# MyRIO_Breakout_Gamma2c.net
KiCad netlist of a schematic drawn in EAGLE
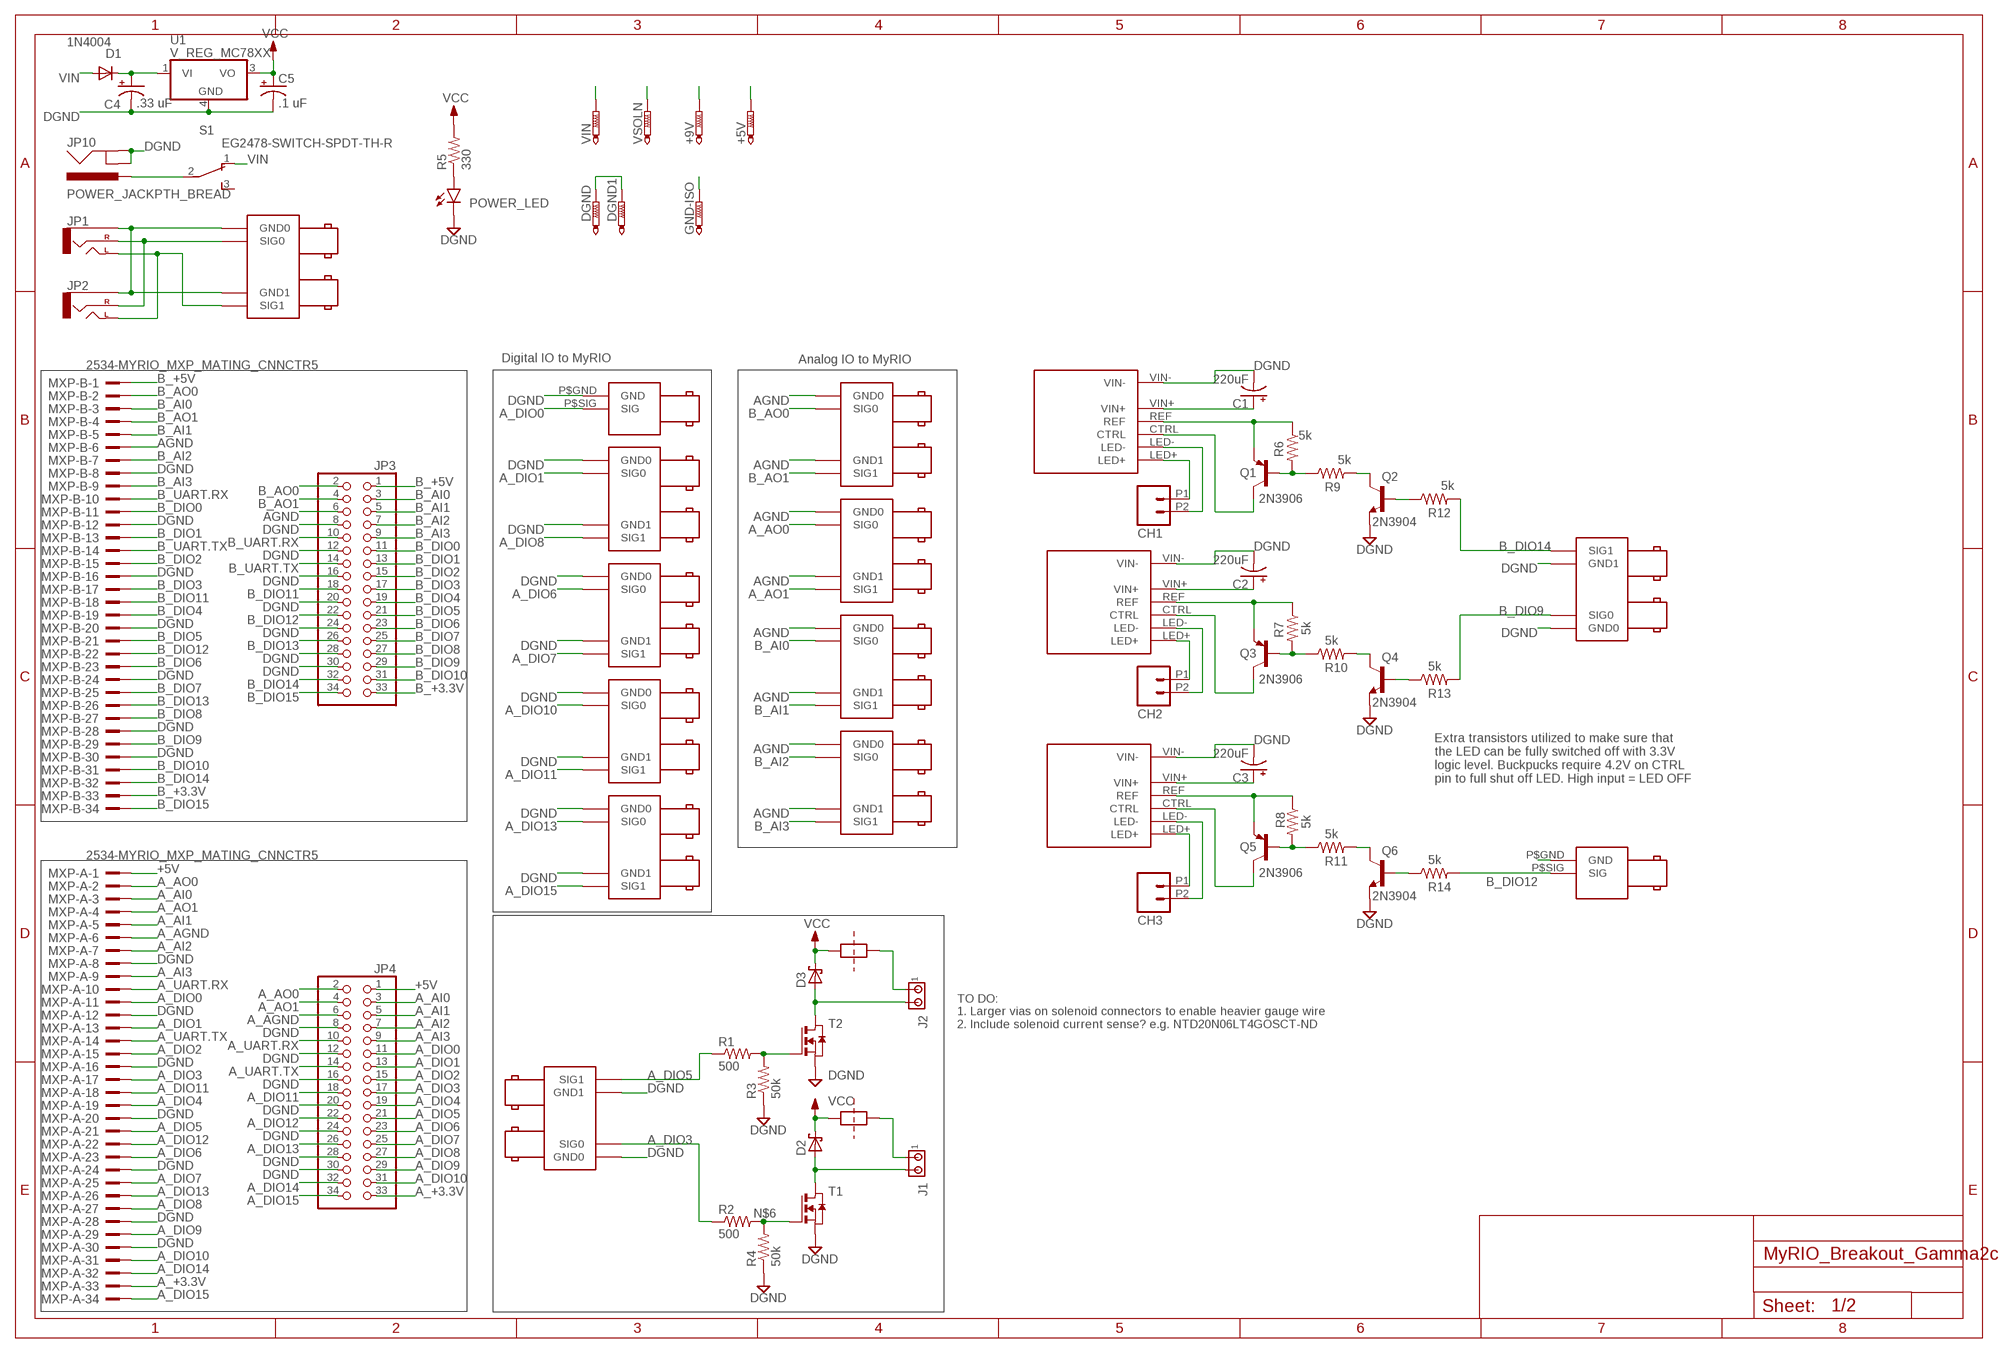
[diagram p0: schematic, sheet 1]
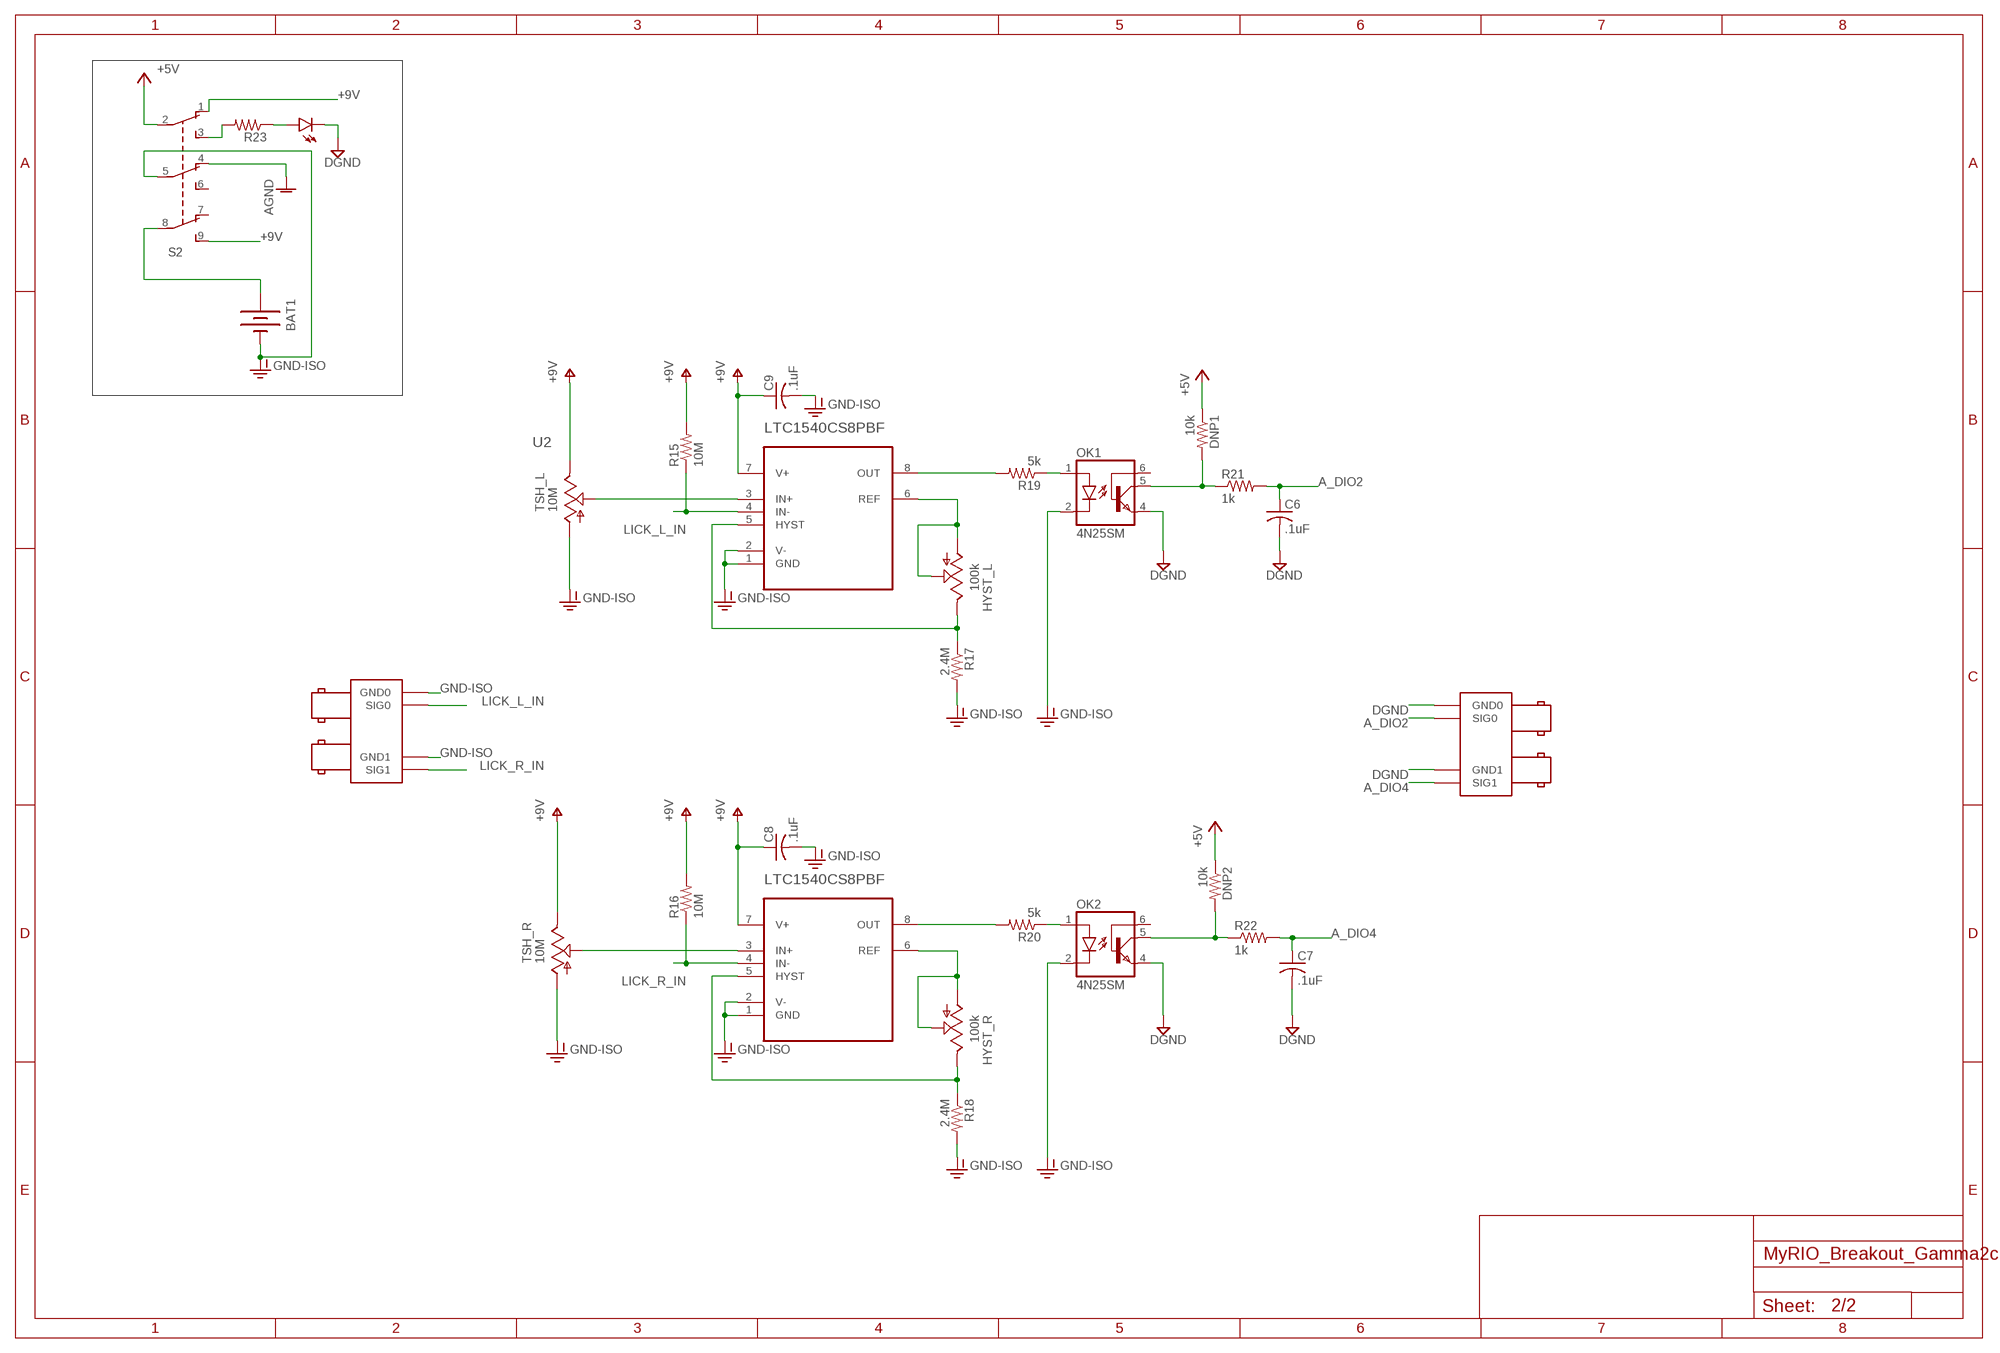
[diagram p1: schematic, sheet 2]

(export (version "E")
  (design (tool "Eeschema 10.0.6"))
  (components
    (comp (ref "BAT1")
      (value "BATTERY9V")
      (footprint "eagle-import:BATTCON_9V")
      (libsource (lib "eagle-import") (part "BATTERY9V"))
    )
    (comp (ref "C6")
      (value ".1uF")
      (footprint "eagle-import:C0805")
      (libsource (lib "eagle-import") (part "C-USC0805"))
    )
    (comp (ref "C7")
      (value ".1uF")
      (footprint "eagle-import:C0805")
      (fields (field (name "SPICEPREFIX") "C"))
      (libsource (lib "eagle-import") (part "C-USC0805"))
    )
    (comp (ref "C8")
      (value ".1uF")
      (footprint "eagle-import:C0805")
      (fields (field (name "SPICEPREFIX") "C"))
      (libsource (lib "eagle-import") (part "C-USC0805"))
    )
    (comp (ref "C9")
      (value ".1uF")
      (footprint "eagle-import:C0805")
      (fields (field (name "SPICEPREFIX") "C"))
      (libsource (lib "eagle-import") (part "C-USC0805"))
    )
    (comp (ref "DNP1")
      (value "10k")
      (footprint "eagle-import:M0805")
      (libsource (lib "eagle-import") (part "R-US_M0805"))
    )
    (comp (ref "DNP2")
      (value "10k")
      (footprint "eagle-import:M0805")
      (fields (field (name "SPICEPREFIX") "R"))
      (libsource (lib "eagle-import") (part "R-US_M0805"))
    )
    (comp (ref "HYST_L")
      (value "100k")
      (footprint "eagle-import:B25P")
      (libsource (lib "eagle-import") (part "TRIM_US-B25P"))
    )
    (comp (ref "HYST_R")
      (value "100k")
      (footprint "eagle-import:B25P")
      (fields (field (name "SPICEPREFIX") "J"))
      (libsource (lib "eagle-import") (part "TRIM_US-B25P"))
    )
    (comp (ref "ISOLATED")
      (value "LED3MM")
      (footprint "eagle-import:LED3MM")
      (libsource (lib "eagle-import") (part "LED3MM"))
    )
    (comp (ref "LICK")
      (value "BNC_RIGHT_ANGLE_DOUBLE")
      (footprint "eagle-import:BNC_RIGHT_ANGLE_DOUBLE")
      (libsource (lib "eagle-import") (part "BNC_RIGHT_ANGLE_DOUBLE"))
    )
    (comp (ref "LICK_INPUTS")
      (value "BNC_RIGHT_ANGLE_DOUBLE")
      (footprint "eagle-import:BNC_RIGHT_ANGLE_DOUBLE")
      (libsource (lib "eagle-import") (part "BNC_RIGHT_ANGLE_DOUBLE"))
    )
    (comp (ref "OK1")
      (value "4N25SM")
      (footprint "eagle-import:DIL6-SMD")
      (fields (field (name "MF") "FAIRCHILD SEMICONDUCTOR"))
      (libsource (lib "eagle-import") (part "4N?MS25"))
    )
    (comp (ref "OK2")
      (value "4N25SM")
      (footprint "eagle-import:DIL6-SMD")
      (fields (field (name "MF") "FAIRCHILD SEMICONDUCTOR") (field (name "SPICEPREFIX") "X"))
      (libsource (lib "eagle-import") (part "4N?MS25"))
    )
    (comp (ref "R15")
      (value "10M")
      (footprint "eagle-import:M0805")
      (fields (field (name "SPICEPREFIX") "R"))
      (libsource (lib "eagle-import") (part "R-US_M0805"))
    )
    (comp (ref "R16")
      (value "10M")
      (footprint "eagle-import:M0805")
      (fields (field (name "SPICEPREFIX") "R"))
      (libsource (lib "eagle-import") (part "R-US_M0805"))
    )
    (comp (ref "R17")
      (value "2.4M")
      (footprint "eagle-import:M0805")
      (libsource (lib "eagle-import") (part "R-US_M0805"))
    )
    (comp (ref "R18")
      (value "2.4M")
      (footprint "eagle-import:M0805")
      (fields (field (name "SPICEPREFIX") "R"))
      (libsource (lib "eagle-import") (part "R-US_M0805"))
    )
    (comp (ref "R19")
      (value "5k")
      (footprint "eagle-import:M0805")
      (libsource (lib "eagle-import") (part "R-US_M0805"))
    )
    (comp (ref "R20")
      (value "5k")
      (footprint "eagle-import:M0805")
      (fields (field (name "SPICEPREFIX") "R"))
      (libsource (lib "eagle-import") (part "R-US_M0805"))
    )
    (comp (ref "R21")
      (value "1k")
      (footprint "eagle-import:M0805")
      (libsource (lib "eagle-import") (part "R-US_M0805"))
    )
    (comp (ref "R22")
      (value "1k")
      (footprint "eagle-import:M0805")
      (fields (field (name "SPICEPREFIX") "R"))
      (libsource (lib "eagle-import") (part "R-US_M0805"))
    )
    (comp (ref "R23")
      (value "330")
      (footprint "eagle-import:0207_10")
      (libsource (lib "eagle-import") (part "R-US_0207/10"))
    )
    (comp (ref "S2")
      (value "SWITCH-3PDT-TH-V")
      (footprint "eagle-import:NKK-M20-9PIN-VERTICAL")
      (libsource (lib "eagle-import") (part "SWITCH-3PDT-TH-V"))
    )
    (comp (ref "TSH_L")
      (value "10M")
      (footprint "eagle-import:B25P")
      (libsource (lib "eagle-import") (part "TRIM_US-B25P"))
    )
    (comp (ref "TSH_R")
      (value "10M")
      (footprint "eagle-import:B25P")
      (libsource (lib "eagle-import") (part "TRIM_US-B25P"))
    )
    (comp (ref "U2")
      (value "LTC1540CS8PBF")
      (footprint "eagle-import:SOIC127P600X175-8N")
      (fields (field (name "MF") "Linear Technology/Analog") (field (name "MP") "LTC1540CS8#PBF"))
      (libsource (lib "eagle-import") (part "LTC1540CS8PBF"))
    )
    (comp (ref "U3")
      (value "LTC1540CS8PBF")
      (footprint "eagle-import:SOIC127P600X175-8N")
      (fields
        (field (name "MF") "Linear Technology/Analog")
        (field (name "MP") "LTC1540CS8#PBF")
        (field (name "SPICEPREFIX") "X")
      )
      (libsource (lib "eagle-import") (part "LTC1540CS8PBF"))
    )
    (comp (ref "+5V")
      (value "PTR1PAD1-13Y")
      (footprint "eagle-import:P1-13Y")
      (libsource (lib "eagle-import") (part "PTR1PAD1-13Y"))
    )
    (comp (ref "+9V")
      (value "PTR1PAD1-13Y")
      (footprint "eagle-import:P1-13Y")
      (libsource (lib "eagle-import") (part "PTR1PAD1-13Y"))
    )
    (comp (ref "AAO_0,1")
      (value "BNC_RIGHT_ANGLE_DOUBLE")
      (footprint "eagle-import:BNC_RIGHT_ANGLE_DOUBLE")
      (libsource (lib "eagle-import") (part "BNC_RIGHT_ANGLE_DOUBLE"))
    )
    (comp (ref "ACTV_REC")
      (value "BNC_RIGHT_ANGLE")
      (footprint "eagle-import:BNC_RIGHT_ANGLE")
      (libsource (lib "eagle-import") (part "BNC_RIGHT_ANGLE"))
    )
    (comp (ref "AUDIO")
      (value "BNC_RIGHT_ANGLE_DOUBLE")
      (footprint "eagle-import:BNC_RIGHT_ANGLE_DOUBLE")
      (libsource (lib "eagle-import") (part "BNC_RIGHT_ANGLE_DOUBLE"))
    )
    (comp (ref "BAI_0,1")
      (value "BNC_RIGHT_ANGLE_DOUBLE")
      (footprint "eagle-import:BNC_RIGHT_ANGLE_DOUBLE")
      (libsource (lib "eagle-import") (part "BNC_RIGHT_ANGLE_DOUBLE"))
    )
    (comp (ref "BAI_2,3")
      (value "BNC_RIGHT_ANGLE_DOUBLE")
      (footprint "eagle-import:BNC_RIGHT_ANGLE_DOUBLE")
      (libsource (lib "eagle-import") (part "BNC_RIGHT_ANGLE_DOUBLE"))
    )
    (comp (ref "BAO_0,1")
      (value "BNC_RIGHT_ANGLE_DOUBLE")
      (footprint "eagle-import:BNC_RIGHT_ANGLE_DOUBLE")
      (libsource (lib "eagle-import") (part "BNC_RIGHT_ANGLE_DOUBLE"))
    )
    (comp (ref "BUCKPUCK1")
      (value "BUCKPUCK-350-I")
      (footprint "eagle-import:BUCKPUCK_I")
      (libsource (lib "eagle-import") (part "BUCKPUCK--?I350"))
    )
    (comp (ref "BUCKPUCK2")
      (value "BUCKPUCK-350-I")
      (footprint "eagle-import:BUCKPUCK_I")
      (libsource (lib "eagle-import") (part "BUCKPUCK--?I350"))
    )
    (comp (ref "BUCKPUCK3")
      (value "BUCKPUCK-350-I")
      (footprint "eagle-import:BUCKPUCK_I")
      (libsource (lib "eagle-import") (part "BUCKPUCK--?I350"))
    )
    (comp (ref "C1")
      (value "220uF")
      (footprint "eagle-import:E5-10,5")
      (libsource (lib "eagle-import") (part "CPOL-USE5-10.5"))
    )
    (comp (ref "C2")
      (value "220uF")
      (footprint "eagle-import:E5-10,5")
      (libsource (lib "eagle-import") (part "CPOL-USE5-10.5"))
    )
    (comp (ref "C3")
      (value "220uF")
      (footprint "eagle-import:E5-10,5")
      (libsource (lib "eagle-import") (part "CPOL-USE5-10.5"))
    )
    (comp (ref "C4")
      (value ".33 uF")
      (footprint "eagle-import:E2,5-5")
      (libsource (lib "eagle-import") (part "CPOL-USE2.5-5"))
    )
    (comp (ref "C5")
      (value ".1 uF")
      (footprint "eagle-import:E2,5-5")
      (libsource (lib "eagle-import") (part "CPOL-USE2.5-5"))
    )
    (comp (ref "CAMERA")
      (value "BNC_RIGHT_ANGLE_DOUBLE")
      (footprint "eagle-import:BNC_RIGHT_ANGLE_DOUBLE")
      (libsource (lib "eagle-import") (part "BNC_RIGHT_ANGLE_DOUBLE"))
    )
    (comp (ref "CH1")
      (value "M022.54MM_SCREWTERM")
      (footprint "eagle-import:1X02_2.54_SCREWTERM")
      (libsource (lib "eagle-import") (part "M022.54MM_SCREWTERM"))
    )
    (comp (ref "CH2")
      (value "M022.54MM_SCREWTERM")
      (footprint "eagle-import:1X02_2.54_SCREWTERM")
      (libsource (lib "eagle-import") (part "M022.54MM_SCREWTERM"))
    )
    (comp (ref "CH3")
      (value "M022.54MM_SCREWTERM")
      (footprint "eagle-import:1X02_2.54_SCREWTERM")
      (libsource (lib "eagle-import") (part "M022.54MM_SCREWTERM"))
    )
    (comp (ref "D1")
      (value "1N4004")
      (footprint "eagle-import:DO41-10")
      (libsource (lib "eagle-import") (part "1N4004"))
    )
    (comp (ref "D2")
      (value "SCHOTTKY-DIODE")
      (footprint "eagle-import:DIODE_SMB")
      (libsource (lib "eagle-import") (part "SCHOTTKY-DIODE"))
    )
    (comp (ref "D3")
      (value "SCHOTTKY-DIODE")
      (footprint "eagle-import:DIODE_SMB")
      (libsource (lib "eagle-import") (part "SCHOTTKY-DIODE"))
    )
    (comp (ref "DGND")
      (value "PTR1PAD1-13Y")
      (footprint "eagle-import:P1-13Y")
      (libsource (lib "eagle-import") (part "PTR1PAD1-13Y"))
    )
    (comp (ref "DGND1")
      (value "PTR1PAD1-13Y")
      (footprint "eagle-import:P1-13Y")
      (libsource (lib "eagle-import") (part "PTR1PAD1-13Y"))
    )
    (comp (ref "D_FREE1_2")
      (value "BNC_RIGHT_ANGLE_DOUBLE")
      (footprint "eagle-import:BNC_RIGHT_ANGLE_DOUBLE")
      (libsource (lib "eagle-import") (part "BNC_RIGHT_ANGLE_DOUBLE"))
    )
    (comp (ref "D_FREE3_4")
      (value "BNC_RIGHT_ANGLE_DOUBLE")
      (footprint "eagle-import:BNC_RIGHT_ANGLE_DOUBLE")
      (libsource (lib "eagle-import") (part "BNC_RIGHT_ANGLE_DOUBLE"))
    )
    (comp (ref "GND-ISO")
      (value "PTR1PAD1-13Y")
      (footprint "eagle-import:P1-13Y")
      (libsource (lib "eagle-import") (part "PTR1PAD1-13Y"))
    )
    (comp (ref "J1")
      (value "MTA02-100")
      (footprint "eagle-import:10X02MTA")
      (libsource (lib "eagle-import") (part "MTA02-100"))
    )
    (comp (ref "J2")
      (value "MTA02-100")
      (footprint "eagle-import:10X02MTA")
      (libsource (lib "eagle-import") (part "MTA02-100"))
    )
    (comp (ref "JP1")
      (value "AUDIO-JACKPTH")
      (footprint "eagle-import:AUDIO-JACK")
      (libsource (lib "eagle-import") (part "AUDIO-JACKPTH"))
    )
    (comp (ref "JP2")
      (value "AUDIO-JACKPTH")
      (footprint "eagle-import:AUDIO-JACK")
      (libsource (lib "eagle-import") (part "AUDIO-JACKPTH"))
    )
    (comp (ref "JP3")
      (value "PINHD-2X17")
      (footprint "eagle-import:2X17")
      (libsource (lib "eagle-import") (part "PINHD-2X17"))
    )
    (comp (ref "JP4")
      (value "PINHD-2X17")
      (footprint "eagle-import:2X17")
      (libsource (lib "eagle-import") (part "PINHD-2X17"))
    )
    (comp (ref "JP5")
      (value "CUTABLE_RESISTOR_JUMPER1206")
      (footprint "eagle-import:1206_WITH_TRACE")
      (libsource (lib "eagle-import") (part "CUTABLE_RESISTOR_JUMPER1206"))
    )
    (comp (ref "JP6")
      (value "CUTABLE_RESISTOR_JUMPER1206")
      (footprint "eagle-import:1206_WITH_TRACE")
      (libsource (lib "eagle-import") (part "CUTABLE_RESISTOR_JUMPER1206"))
    )
    (comp (ref "JP10")
      (value "POWER_JACKPTH_BREAD")
      (footprint "eagle-import:POWER_JACK_PTH_BREAD")
      (libsource (lib "eagle-import") (part "POWER_JACKPTH_BREAD"))
    )
    (comp (ref "LED_CUE_3")
      (value "BNC_RIGHT_ANGLE")
      (footprint "eagle-import:BNC_RIGHT_ANGLE")
      (libsource (lib "eagle-import") (part "BNC_RIGHT_ANGLE"))
    )
    (comp (ref "LED_MASK_1,2")
      (value "BNC_RIGHT_ANGLE_DOUBLE")
      (footprint "eagle-import:BNC_RIGHT_ANGLE_DOUBLE")
      (libsource (lib "eagle-import") (part "BNC_RIGHT_ANGLE_DOUBLE"))
    )
    (comp (ref "MXP-A")
      (value "2534-MYRIO_MXP_MATING_CNNCTR5")
      (footprint "eagle-import:PAK100_2500-5-34-MXP_CONNCTR")
      (libsource (lib "eagle-import") (part "2534-MYRIO_MXP_MATING_CNNCTR5"))
    )
    (comp (ref "MXP-B")
      (value "2534-MYRIO_MXP_MATING_CNNCTR5")
      (footprint "eagle-import:PAK100_2500-5-34-MXP_CONNCTR")
      (libsource (lib "eagle-import") (part "2534-MYRIO_MXP_MATING_CNNCTR5"))
    )
    (comp (ref "POWER_LED")
      (value "LED3MM")
      (footprint "eagle-import:LED3MM")
      (libsource (lib "eagle-import") (part "LED3MM"))
    )
    (comp (ref "Q1")
      (value "2N3906")
      (footprint "eagle-import:SOT23-BEC")
      (libsource (lib "eagle-import") (part "-PNP-SOT23-BECMMBT3906LT1"))
    )
    (comp (ref "Q2")
      (value "2N3904")
      (footprint "eagle-import:SOT23-BEC")
      (libsource (lib "eagle-import") (part "-NPN-SOT23-BECMMBT3904LT1"))
    )
    (comp (ref "Q3")
      (value "2N3906")
      (footprint "eagle-import:SOT23-BEC")
      (libsource (lib "eagle-import") (part "-PNP-SOT23-BECMMBT3906LT1"))
    )
    (comp (ref "Q4")
      (value "2N3904")
      (footprint "eagle-import:SOT23-BEC")
      (libsource (lib "eagle-import") (part "-NPN-SOT23-BECMMBT3904LT1"))
    )
    (comp (ref "Q5")
      (value "2N3906")
      (footprint "eagle-import:SOT23-BEC")
      (libsource (lib "eagle-import") (part "-PNP-SOT23-BECMMBT3906LT1"))
    )
    (comp (ref "Q6")
      (value "2N3904")
      (footprint "eagle-import:SOT23-BEC")
      (libsource (lib "eagle-import") (part "-NPN-SOT23-BECMMBT3904LT1"))
    )
    (comp (ref "R1")
      (value "500")
      (footprint "eagle-import:M1206")
      (libsource (lib "eagle-import") (part "R-US_M1206"))
    )
    (comp (ref "R2")
      (value "500")
      (footprint "eagle-import:M1206")
      (libsource (lib "eagle-import") (part "R-US_M1206"))
    )
    (comp (ref "R3")
      (value "50k")
      (footprint "eagle-import:M1206")
      (libsource (lib "eagle-import") (part "R-US_M1206"))
    )
    (comp (ref "R4")
      (value "50k")
      (footprint "eagle-import:M1206")
      (libsource (lib "eagle-import") (part "R-US_M1206"))
    )
    (comp (ref "R5")
      (value "330")
      (footprint "eagle-import:0207_10")
      (libsource (lib "eagle-import") (part "R-US_0207/10"))
    )
    (comp (ref "R6")
      (value "5k")
      (footprint "eagle-import:0805S")
      (libsource (lib "eagle-import") (part "RESISTOR_SM0805S"))
    )
    (comp (ref "R7")
      (value "5k")
      (footprint "eagle-import:0805S")
      (libsource (lib "eagle-import") (part "RESISTOR_SM0805S"))
    )
    (comp (ref "R8")
      (value "5k")
      (footprint "eagle-import:0805S")
      (libsource (lib "eagle-import") (part "RESISTOR_SM0805S"))
    )
    (comp (ref "R9")
      (value "5k")
      (footprint "eagle-import:0805S")
      (libsource (lib "eagle-import") (part "RESISTOR_SM0805S"))
    )
    (comp (ref "R10")
      (value "5k")
      (footprint "eagle-import:0805S")
      (libsource (lib "eagle-import") (part "RESISTOR_SM0805S"))
    )
    (comp (ref "R11")
      (value "5k")
      (footprint "eagle-import:0805S")
      (libsource (lib "eagle-import") (part "RESISTOR_SM0805S"))
    )
    (comp (ref "R12")
      (value "5k")
      (footprint "eagle-import:0805S")
      (libsource (lib "eagle-import") (part "RESISTOR_SM0805S"))
    )
    (comp (ref "R13")
      (value "5k")
      (footprint "eagle-import:0805S")
      (libsource (lib "eagle-import") (part "RESISTOR_SM0805S"))
    )
    (comp (ref "R14")
      (value "5k")
      (footprint "eagle-import:0805S")
      (libsource (lib "eagle-import") (part "RESISTOR_SM0805S"))
    )
    (comp (ref "S1")
      (value "EG2478-SWITCH-SPDT-TH-R")
      (footprint "eagle-import:ESWITCH_500-SSP1M6")
      (libsource (lib "eagle-import") (part "EG2478-SWITCH-SPDT-TH-R"))
    )
    (comp (ref "SHUTTER")
      (value "BNC_RIGHT_ANGLE_DOUBLE")
      (footprint "eagle-import:BNC_RIGHT_ANGLE_DOUBLE")
      (libsource (lib "eagle-import") (part "BNC_RIGHT_ANGLE_DOUBLE"))
    )
    (comp (ref "SLN")
      (value "BNC_RIGHT_ANGLE_DOUBLE")
      (footprint "eagle-import:BNC_RIGHT_ANGLE_DOUBLE")
      (libsource (lib "eagle-import") (part "BNC_RIGHT_ANGLE_DOUBLE"))
    )
    (comp (ref "T1")
      (value "NMOSSOT223")
      (footprint "eagle-import:SOT223")
      (libsource (lib "eagle-import") (part "NMOSSOT223"))
    )
    (comp (ref "T2")
      (value "NMOSSOT223")
      (footprint "eagle-import:SOT223")
      (libsource (lib "eagle-import") (part "NMOSSOT223"))
    )
    (comp (ref "U1")
      (value "V_REG_MC78XX")
      (footprint "eagle-import:DPAK")
      (libsource (lib "eagle-import") (part "V_REG_MC78XX"))
    )
    (comp (ref "VIN")
      (value "PTR1PAD1-13Y")
      (footprint "eagle-import:P1-13Y")
      (libsource (lib "eagle-import") (part "PTR1PAD1-13Y"))
    )
    (comp (ref "VSOLN")
      (value "PTR1PAD1-13Y")
      (footprint "eagle-import:P1-13Y")
      (libsource (lib "eagle-import") (part "PTR1PAD1-13Y"))
    )
  )
  (nets
    (net (code "1") (name "+5V") (class "Default")
      (node (ref "+5V") (pin "TP") (pinfunction "TP_TP") (pintype "input"))
      (node (ref "DNP1") (pin "1") (pinfunction "1_1") (pintype "passive"))
      (node (ref "DNP2") (pin "1") (pinfunction "1_1") (pintype "passive"))
      (node (ref "JP4") (pin "1") (pinfunction "1_1") (pintype "passive"))
      (node (ref "MXP-A") (pin "1") (pinfunction "KL_1") (pintype "passive"))
      (node (ref "S2") (pin "2") (pinfunction "P1_2") (pintype "passive"))
    )
    (net (code "2") (name "+9V") (class "Default")
      (node (ref "+9V") (pin "TP") (pinfunction "TP_TP") (pintype "input"))
      (node (ref "C8") (pin "1") (pinfunction "1_1") (pintype "passive"))
      (node (ref "C9") (pin "1") (pinfunction "1_1") (pintype "passive"))
      (node (ref "R15") (pin "2") (pinfunction "2_2") (pintype "passive"))
      (node (ref "R16") (pin "2") (pinfunction "2_2") (pintype "passive"))
      (node (ref "S2") (pin "1") (pinfunction "O1_1") (pintype "passive"))
      (node (ref "S2") (pin "9") (pinfunction "S3_9") (pintype "passive"))
      (node (ref "TSH_L") (pin "E") (pinfunction "E_E") (pintype "passive"))
      (node (ref "TSH_R") (pin "E") (pinfunction "E_E") (pintype "passive"))
      (node (ref "U2") (pin "7") (pinfunction "V+_7") (pintype "power_in"))
      (node (ref "U3") (pin "7") (pinfunction "V+_7") (pintype "power_in"))
    )
    (net (code "3") (name "AGND") (class "Default")
      (node (ref "AAO_0,1") (pin "P$GND0") (pinfunction "GND0_P$GND0") (pintype "bidirectional"))
      (node (ref "AAO_0,1") (pin "P$GND1") (pinfunction "GND1_P$GND1") (pintype "bidirectional"))
      (node (ref "BAI_0,1") (pin "P$GND0") (pinfunction "GND0_P$GND0") (pintype "bidirectional"))
      (node (ref "BAI_0,1") (pin "P$GND1") (pinfunction "GND1_P$GND1") (pintype "bidirectional"))
      (node (ref "BAI_2,3") (pin "P$GND0") (pinfunction "GND0_P$GND0") (pintype "bidirectional"))
      (node (ref "BAI_2,3") (pin "P$GND1") (pinfunction "GND1_P$GND1") (pintype "bidirectional"))
      (node (ref "BAO_0,1") (pin "P$GND0") (pinfunction "GND0_P$GND0") (pintype "bidirectional"))
      (node (ref "BAO_0,1") (pin "P$GND1") (pinfunction "GND1_P$GND1") (pintype "bidirectional"))
      (node (ref "JP3") (pin "6") (pinfunction "6_6") (pintype "passive"))
      (node (ref "MXP-B") (pin "6") (pinfunction "KL_6") (pintype "passive"))
      (node (ref "S2") (pin "4") (pinfunction "O2_4") (pintype "passive"))
    )
    (net (code "4") (name "A_+3.3V") (class "Default")
      (node (ref "JP4") (pin "33") (pinfunction "33_33") (pintype "passive"))
      (node (ref "MXP-A") (pin "33") (pinfunction "KL_33") (pintype "passive"))
    )
    (net (code "5") (name "A_AGND") (class "Default")
      (node (ref "JP4") (pin "6") (pinfunction "6_6") (pintype "passive"))
      (node (ref "MXP-A") (pin "6") (pinfunction "KL_6") (pintype "passive"))
    )
    (net (code "6") (name "A_AI0") (class "Default")
      (node (ref "JP4") (pin "3") (pinfunction "3_3") (pintype "passive"))
      (node (ref "MXP-A") (pin "3") (pinfunction "KL_3") (pintype "passive"))
    )
    (net (code "7") (name "A_AI1") (class "Default")
      (node (ref "JP4") (pin "5") (pinfunction "5_5") (pintype "passive"))
      (node (ref "MXP-A") (pin "5") (pinfunction "KL_5") (pintype "passive"))
    )
    (net (code "8") (name "A_AI2") (class "Default")
      (node (ref "JP4") (pin "7") (pinfunction "7_7") (pintype "passive"))
      (node (ref "MXP-A") (pin "7") (pinfunction "KL_7") (pintype "passive"))
    )
    (net (code "9") (name "A_AI3") (class "Default")
      (node (ref "JP4") (pin "9") (pinfunction "9_9") (pintype "passive"))
      (node (ref "MXP-A") (pin "9") (pinfunction "KL_9") (pintype "passive"))
    )
    (net (code "10") (name "A_AO0") (class "Default")
      (node (ref "AAO_0,1") (pin "P$SIG0") (pinfunction "SIG0_P$SIG0") (pintype "bidirectional"))
      (node (ref "JP4") (pin "2") (pinfunction "2_2") (pintype "passive"))
      (node (ref "MXP-A") (pin "2") (pinfunction "KL_2") (pintype "passive"))
    )
    (net (code "11") (name "A_AO1") (class "Default")
      (node (ref "AAO_0,1") (pin "P$SIG1") (pinfunction "SIG1_P$SIG1") (pintype "bidirectional"))
      (node (ref "JP4") (pin "4") (pinfunction "4_4") (pintype "passive"))
      (node (ref "MXP-A") (pin "4") (pinfunction "KL_4") (pintype "passive"))
    )
    (net (code "12") (name "A_DIO0") (class "Default")
      (node (ref "ACTV_REC") (pin "P$SIG") (pinfunction "SIG_P$SIG") (pintype "bidirectional"))
      (node (ref "JP4") (pin "11") (pinfunction "11_11") (pintype "passive"))
      (node (ref "MXP-A") (pin "11") (pinfunction "KL_11") (pintype "passive"))
    )
    (net (code "13") (name "A_DIO1") (class "Default")
      (node (ref "CAMERA") (pin "P$SIG0") (pinfunction "SIG0_P$SIG0") (pintype "bidirectional"))
      (node (ref "JP4") (pin "13") (pinfunction "13_13") (pintype "passive"))
      (node (ref "MXP-A") (pin "13") (pinfunction "KL_13") (pintype "passive"))
    )
    (net (code "14") (name "A_DIO2") (class "Default")
      (node (ref "C6") (pin "1") (pinfunction "1_1") (pintype "passive"))
      (node (ref "JP4") (pin "15") (pinfunction "15_15") (pintype "passive"))
      (node (ref "LICK") (pin "P$SIG0") (pinfunction "SIG0_P$SIG0") (pintype "bidirectional"))
      (node (ref "MXP-A") (pin "15") (pinfunction "KL_15") (pintype "passive"))
      (node (ref "R21") (pin "2") (pinfunction "2_2") (pintype "passive"))
    )
    (net (code "15") (name "A_DIO3") (class "Default")
      (node (ref "JP4") (pin "17") (pinfunction "17_17") (pintype "passive"))
      (node (ref "MXP-A") (pin "17") (pinfunction "KL_17") (pintype "passive"))
      (node (ref "R2") (pin "1") (pinfunction "1_1") (pintype "passive"))
      (node (ref "SLN") (pin "P$SIG0") (pinfunction "SIG0_P$SIG0") (pintype "bidirectional"))
    )
    (net (code "16") (name "A_DIO4") (class "Default")
      (node (ref "C7") (pin "1") (pinfunction "1_1") (pintype "passive"))
      (node (ref "JP4") (pin "19") (pinfunction "19_19") (pintype "passive"))
      (node (ref "LICK") (pin "P$SIG1") (pinfunction "SIG1_P$SIG1") (pintype "bidirectional"))
      (node (ref "MXP-A") (pin "19") (pinfunction "KL_19") (pintype "passive"))
      (node (ref "R22") (pin "2") (pinfunction "2_2") (pintype "passive"))
    )
    (net (code "17") (name "A_DIO5") (class "Default")
      (node (ref "JP4") (pin "21") (pinfunction "21_21") (pintype "passive"))
      (node (ref "MXP-A") (pin "21") (pinfunction "KL_21") (pintype "passive"))
      (node (ref "R1") (pin "1") (pinfunction "1_1") (pintype "passive"))
      (node (ref "SLN") (pin "P$SIG1") (pinfunction "SIG1_P$SIG1") (pintype "bidirectional"))
    )
    (net (code "18") (name "A_DIO6") (class "Default")
      (node (ref "JP4") (pin "23") (pinfunction "23_23") (pintype "passive"))
      (node (ref "MXP-A") (pin "23") (pinfunction "KL_23") (pintype "passive"))
      (node (ref "SHUTTER") (pin "P$SIG0") (pinfunction "SIG0_P$SIG0") (pintype "bidirectional"))
    )
    (net (code "19") (name "A_DIO7") (class "Default")
      (node (ref "JP4") (pin "25") (pinfunction "25_25") (pintype "passive"))
      (node (ref "MXP-A") (pin "25") (pinfunction "KL_25") (pintype "passive"))
      (node (ref "SHUTTER") (pin "P$SIG1") (pinfunction "SIG1_P$SIG1") (pintype "bidirectional"))
    )
    (net (code "20") (name "A_DIO8") (class "Default")
      (node (ref "CAMERA") (pin "P$SIG1") (pinfunction "SIG1_P$SIG1") (pintype "bidirectional"))
      (node (ref "JP4") (pin "27") (pinfunction "27_27") (pintype "passive"))
      (node (ref "MXP-A") (pin "27") (pinfunction "KL_27") (pintype "passive"))
    )
    (net (code "21") (name "A_DIO9") (class "Default")
      (node (ref "JP4") (pin "29") (pinfunction "29_29") (pintype "passive"))
      (node (ref "MXP-A") (pin "29") (pinfunction "KL_29") (pintype "passive"))
    )
    (net (code "22") (name "A_DIO10") (class "Default")
      (node (ref "D_FREE1_2") (pin "P$SIG0") (pinfunction "SIG0_P$SIG0") (pintype "bidirectional"))
      (node (ref "JP4") (pin "31") (pinfunction "31_31") (pintype "passive"))
      (node (ref "MXP-A") (pin "31") (pinfunction "KL_31") (pintype "passive"))
    )
    (net (code "23") (name "A_DIO11") (class "Default")
      (node (ref "D_FREE1_2") (pin "P$SIG1") (pinfunction "SIG1_P$SIG1") (pintype "bidirectional"))
      (node (ref "JP4") (pin "18") (pinfunction "18_18") (pintype "passive"))
      (node (ref "MXP-A") (pin "18") (pinfunction "KL_18") (pintype "passive"))
    )
    (net (code "24") (name "A_DIO12") (class "Default")
      (node (ref "JP4") (pin "22") (pinfunction "22_22") (pintype "passive"))
      (node (ref "MXP-A") (pin "22") (pinfunction "KL_22") (pintype "passive"))
    )
    (net (code "25") (name "A_DIO13") (class "Default")
      (node (ref "D_FREE3_4") (pin "P$SIG0") (pinfunction "SIG0_P$SIG0") (pintype "bidirectional"))
      (node (ref "JP4") (pin "26") (pinfunction "26_26") (pintype "passive"))
      (node (ref "MXP-A") (pin "26") (pinfunction "KL_26") (pintype "passive"))
    )
    (net (code "26") (name "A_DIO14") (class "Default")
      (node (ref "JP4") (pin "32") (pinfunction "32_32") (pintype "passive"))
      (node (ref "MXP-A") (pin "32") (pinfunction "KL_32") (pintype "passive"))
    )
    (net (code "27") (name "A_DIO15") (class "Default")
      (node (ref "D_FREE3_4") (pin "P$SIG1") (pinfunction "SIG1_P$SIG1") (pintype "bidirectional"))
      (node (ref "JP4") (pin "34") (pinfunction "34_34") (pintype "passive"))
      (node (ref "MXP-A") (pin "34") (pinfunction "KL_34") (pintype "passive"))
    )
    (net (code "28") (name "A_UART.RX") (class "Default")
      (node (ref "JP4") (pin "10") (pinfunction "10_10") (pintype "passive"))
      (node (ref "MXP-A") (pin "10") (pinfunction "KL_10") (pintype "passive"))
    )
    (net (code "29") (name "A_UART.TX") (class "Default")
      (node (ref "JP4") (pin "14") (pinfunction "14_14") (pintype "passive"))
      (node (ref "MXP-A") (pin "14") (pinfunction "KL_14") (pintype "passive"))
    )
    (net (code "30") (name "B_+3.3V") (class "Default")
      (node (ref "JP3") (pin "33") (pinfunction "33_33") (pintype "passive"))
      (node (ref "MXP-B") (pin "33") (pinfunction "KL_33") (pintype "passive"))
    )
    (net (code "31") (name "B_+5V") (class "Default")
      (node (ref "JP3") (pin "1") (pinfunction "1_1") (pintype "passive"))
      (node (ref "MXP-B") (pin "1") (pinfunction "KL_1") (pintype "passive"))
    )
    (net (code "32") (name "B_AI0") (class "Default")
      (node (ref "BAI_0,1") (pin "P$SIG0") (pinfunction "SIG0_P$SIG0") (pintype "bidirectional"))
      (node (ref "JP3") (pin "3") (pinfunction "3_3") (pintype "passive"))
      (node (ref "MXP-B") (pin "3") (pinfunction "KL_3") (pintype "passive"))
    )
    (net (code "33") (name "B_AI1") (class "Default")
      (node (ref "BAI_0,1") (pin "P$SIG1") (pinfunction "SIG1_P$SIG1") (pintype "bidirectional"))
      (node (ref "JP3") (pin "5") (pinfunction "5_5") (pintype "passive"))
      (node (ref "MXP-B") (pin "5") (pinfunction "KL_5") (pintype "passive"))
    )
    (net (code "34") (name "B_AI2") (class "Default")
      (node (ref "BAI_2,3") (pin "P$SIG0") (pinfunction "SIG0_P$SIG0") (pintype "bidirectional"))
      (node (ref "JP3") (pin "7") (pinfunction "7_7") (pintype "passive"))
      (node (ref "MXP-B") (pin "7") (pinfunction "KL_7") (pintype "passive"))
    )
    (net (code "35") (name "B_AI3") (class "Default")
      (node (ref "BAI_2,3") (pin "P$SIG1") (pinfunction "SIG1_P$SIG1") (pintype "bidirectional"))
      (node (ref "JP3") (pin "9") (pinfunction "9_9") (pintype "passive"))
      (node (ref "MXP-B") (pin "9") (pinfunction "KL_9") (pintype "passive"))
    )
    (net (code "36") (name "B_AO0") (class "Default")
      (node (ref "BAO_0,1") (pin "P$SIG0") (pinfunction "SIG0_P$SIG0") (pintype "bidirectional"))
      (node (ref "JP3") (pin "2") (pinfunction "2_2") (pintype "passive"))
      (node (ref "MXP-B") (pin "2") (pinfunction "KL_2") (pintype "passive"))
    )
    (net (code "37") (name "B_AO1") (class "Default")
      (node (ref "BAO_0,1") (pin "P$SIG1") (pinfunction "SIG1_P$SIG1") (pintype "bidirectional"))
      (node (ref "JP3") (pin "4") (pinfunction "4_4") (pintype "passive"))
      (node (ref "MXP-B") (pin "4") (pinfunction "KL_4") (pintype "passive"))
    )
    (net (code "38") (name "B_DIO0") (class "Default")
      (node (ref "JP3") (pin "11") (pinfunction "11_11") (pintype "passive"))
      (node (ref "MXP-B") (pin "11") (pinfunction "KL_11") (pintype "passive"))
    )
    (net (code "39") (name "B_DIO1") (class "Default")
      (node (ref "JP3") (pin "13") (pinfunction "13_13") (pintype "passive"))
      (node (ref "MXP-B") (pin "13") (pinfunction "KL_13") (pintype "passive"))
    )
    (net (code "40") (name "B_DIO2") (class "Default")
      (node (ref "JP3") (pin "15") (pinfunction "15_15") (pintype "passive"))
      (node (ref "MXP-B") (pin "15") (pinfunction "KL_15") (pintype "passive"))
    )
    (net (code "41") (name "B_DIO3") (class "Default")
      (node (ref "JP3") (pin "17") (pinfunction "17_17") (pintype "passive"))
      (node (ref "MXP-B") (pin "17") (pinfunction "KL_17") (pintype "passive"))
    )
    (net (code "42") (name "B_DIO4") (class "Default")
      (node (ref "JP3") (pin "19") (pinfunction "19_19") (pintype "passive"))
      (node (ref "MXP-B") (pin "19") (pinfunction "KL_19") (pintype "passive"))
    )
    (net (code "43") (name "B_DIO5") (class "Default")
      (node (ref "JP3") (pin "21") (pinfunction "21_21") (pintype "passive"))
      (node (ref "MXP-B") (pin "21") (pinfunction "KL_21") (pintype "passive"))
    )
    (net (code "44") (name "B_DIO6") (class "Default")
      (node (ref "JP3") (pin "23") (pinfunction "23_23") (pintype "passive"))
      (node (ref "MXP-B") (pin "23") (pinfunction "KL_23") (pintype "passive"))
    )
    (net (code "45") (name "B_DIO7") (class "Default")
      (node (ref "JP3") (pin "25") (pinfunction "25_25") (pintype "passive"))
      (node (ref "MXP-B") (pin "25") (pinfunction "KL_25") (pintype "passive"))
    )
    (net (code "46") (name "B_DIO8") (class "Default")
      (node (ref "JP3") (pin "27") (pinfunction "27_27") (pintype "passive"))
      (node (ref "MXP-B") (pin "27") (pinfunction "KL_27") (pintype "passive"))
    )
    (net (code "47") (name "B_DIO9") (class "Default")
      (node (ref "JP3") (pin "29") (pinfunction "29_29") (pintype "passive"))
      (node (ref "LED_MASK_1,2") (pin "P$SIG0") (pinfunction "SIG0_P$SIG0") (pintype "bidirectional"))
      (node (ref "MXP-B") (pin "29") (pinfunction "KL_29") (pintype "passive"))
      (node (ref "R13") (pin "2") (pinfunction "2_2") (pintype "passive"))
    )
    (net (code "48") (name "B_DIO10") (class "Default")
      (node (ref "JP3") (pin "31") (pinfunction "31_31") (pintype "passive"))
      (node (ref "MXP-B") (pin "31") (pinfunction "KL_31") (pintype "passive"))
    )
    (net (code "49") (name "B_DIO11") (class "Default")
      (node (ref "JP3") (pin "18") (pinfunction "18_18") (pintype "passive"))
      (node (ref "MXP-B") (pin "18") (pinfunction "KL_18") (pintype "passive"))
    )
    (net (code "50") (name "B_DIO12") (class "Default")
      (node (ref "JP3") (pin "22") (pinfunction "22_22") (pintype "passive"))
      (node (ref "LED_CUE_3") (pin "P$SIG") (pinfunction "SIG_P$SIG") (pintype "bidirectional"))
      (node (ref "MXP-B") (pin "22") (pinfunction "KL_22") (pintype "passive"))
      (node (ref "R14") (pin "2") (pinfunction "2_2") (pintype "passive"))
    )
    (net (code "51") (name "B_DIO13") (class "Default")
      (node (ref "JP3") (pin "26") (pinfunction "26_26") (pintype "passive"))
      (node (ref "MXP-B") (pin "26") (pinfunction "KL_26") (pintype "passive"))
    )
    (net (code "52") (name "B_DIO14") (class "Default")
      (node (ref "JP3") (pin "32") (pinfunction "32_32") (pintype "passive"))
      (node (ref "LED_MASK_1,2") (pin "P$SIG1") (pinfunction "SIG1_P$SIG1") (pintype "bidirectional"))
      (node (ref "MXP-B") (pin "32") (pinfunction "KL_32") (pintype "passive"))
      (node (ref "R12") (pin "2") (pinfunction "2_2") (pintype "passive"))
    )
    (net (code "53") (name "B_DIO15") (class "Default")
      (node (ref "JP3") (pin "34") (pinfunction "34_34") (pintype "passive"))
      (node (ref "MXP-B") (pin "34") (pinfunction "KL_34") (pintype "passive"))
    )
    (net (code "54") (name "B_UART.RX") (class "Default")
      (node (ref "JP3") (pin "10") (pinfunction "10_10") (pintype "passive"))
      (node (ref "MXP-B") (pin "10") (pinfunction "KL_10") (pintype "passive"))
    )
    (net (code "55") (name "B_UART.TX") (class "Default")
      (node (ref "JP3") (pin "14") (pinfunction "14_14") (pintype "passive"))
      (node (ref "MXP-B") (pin "14") (pinfunction "KL_14") (pintype "passive"))
    )
    (net (code "56") (name "DGND") (class "Default")
      (node (ref "ACTV_REC") (pin "P$GND") (pinfunction "GND_P$GND") (pintype "bidirectional"))
      (node (ref "BUCKPUCK1") (pin "LED-") (pinfunction "LED-_LED-") (pintype "bidirectional"))
      (node (ref "BUCKPUCK1") (pin "VIN-") (pinfunction "VIN-_VIN-") (pintype "bidirectional"))
      (node (ref "BUCKPUCK2") (pin "LED-") (pinfunction "LED-_LED-") (pintype "bidirectional"))
      (node (ref "BUCKPUCK2") (pin "VIN-") (pinfunction "VIN-_VIN-") (pintype "bidirectional"))
      (node (ref "BUCKPUCK3") (pin "LED-") (pinfunction "LED-_LED-") (pintype "bidirectional"))
      (node (ref "BUCKPUCK3") (pin "VIN-") (pinfunction "VIN-_VIN-") (pintype "bidirectional"))
      (node (ref "C1") (pin "-") (pinfunction "-_-") (pintype "passive"))
      (node (ref "C2") (pin "-") (pinfunction "-_-") (pintype "passive"))
      (node (ref "C3") (pin "-") (pinfunction "-_-") (pintype "passive"))
      (node (ref "C4") (pin "-") (pinfunction "-_-") (pintype "passive"))
      (node (ref "C5") (pin "-") (pinfunction "-_-") (pintype "passive"))
      (node (ref "C6") (pin "2") (pinfunction "2_2") (pintype "passive"))
      (node (ref "C7") (pin "2") (pinfunction "2_2") (pintype "passive"))
      (node (ref "CAMERA") (pin "P$GND0") (pinfunction "GND0_P$GND0") (pintype "bidirectional"))
      (node (ref "CAMERA") (pin "P$GND1") (pinfunction "GND1_P$GND1") (pintype "bidirectional"))
      (node (ref "CH1") (pin "P2") (pinfunction "2_P2") (pintype "passive"))
      (node (ref "CH2") (pin "P2") (pinfunction "2_P2") (pintype "passive"))
      (node (ref "CH3") (pin "P2") (pinfunction "2_P2") (pintype "passive"))
      (node (ref "DGND") (pin "TP") (pinfunction "TP_TP") (pintype "input"))
      (node (ref "DGND1") (pin "TP") (pinfunction "TP_TP") (pintype "input"))
      (node (ref "D_FREE1_2") (pin "P$GND0") (pinfunction "GND0_P$GND0") (pintype "bidirectional"))
      (node (ref "D_FREE1_2") (pin "P$GND1") (pinfunction "GND1_P$GND1") (pintype "bidirectional"))
      (node (ref "D_FREE3_4") (pin "P$GND0") (pinfunction "GND0_P$GND0") (pintype "bidirectional"))
      (node (ref "D_FREE3_4") (pin "P$GND1") (pinfunction "GND1_P$GND1") (pintype "bidirectional"))
      (node (ref "ISOLATED") (pin "K") (pinfunction "C_K") (pintype "passive"))
      (node (ref "JP10") (pin "GND") (pinfunction "GND_GND") (pintype "bidirectional"))
      (node (ref "JP10") (pin "GNDBREAK") (pinfunction "GNDBREAK_GNDBREAK") (pintype "bidirectional"))
      (node (ref "JP3") (pin "12") (pinfunction "12_12") (pintype "passive"))
      (node (ref "JP3") (pin "16") (pinfunction "16_16") (pintype "passive"))
      (node (ref "JP3") (pin "20") (pinfunction "20_20") (pintype "passive"))
      (node (ref "JP3") (pin "24") (pinfunction "24_24") (pintype "passive"))
      (node (ref "JP3") (pin "28") (pinfunction "28_28") (pintype "passive"))
      (node (ref "JP3") (pin "30") (pinfunction "30_30") (pintype "passive"))
      (node (ref "JP3") (pin "8") (pinfunction "8_8") (pintype "passive"))
      (node (ref "JP4") (pin "12") (pinfunction "12_12") (pintype "passive"))
      (node (ref "JP4") (pin "16") (pinfunction "16_16") (pintype "passive"))
      (node (ref "JP4") (pin "20") (pinfunction "20_20") (pintype "passive"))
      (node (ref "JP4") (pin "24") (pinfunction "24_24") (pintype "passive"))
      (node (ref "JP4") (pin "28") (pinfunction "28_28") (pintype "passive"))
      (node (ref "JP4") (pin "30") (pinfunction "30_30") (pintype "passive"))
      (node (ref "JP4") (pin "8") (pinfunction "8_8") (pintype "passive"))
      (node (ref "LED_CUE_3") (pin "P$GND") (pinfunction "GND_P$GND") (pintype "bidirectional"))
      (node (ref "LED_MASK_1,2") (pin "P$GND0") (pinfunction "GND0_P$GND0") (pintype "bidirectional"))
      (node (ref "LED_MASK_1,2") (pin "P$GND1") (pinfunction "GND1_P$GND1") (pintype "bidirectional"))
      (node (ref "LICK") (pin "P$GND0") (pinfunction "GND0_P$GND0") (pintype "bidirectional"))
      (node (ref "LICK") (pin "P$GND1") (pinfunction "GND1_P$GND1") (pintype "bidirectional"))
      (node (ref "MXP-A") (pin "12") (pinfunction "KL_12") (pintype "passive"))
      (node (ref "MXP-A") (pin "16") (pinfunction "KL_16") (pintype "passive"))
      (node (ref "MXP-A") (pin "20") (pinfunction "KL_20") (pintype "passive"))
      (node (ref "MXP-A") (pin "24") (pinfunction "KL_24") (pintype "passive"))
      (node (ref "MXP-A") (pin "28") (pinfunction "KL_28") (pintype "passive"))
      (node (ref "MXP-A") (pin "30") (pinfunction "KL_30") (pintype "passive"))
      (node (ref "MXP-A") (pin "8") (pinfunction "KL_8") (pintype "passive"))
      (node (ref "MXP-B") (pin "12") (pinfunction "KL_12") (pintype "passive"))
      (node (ref "MXP-B") (pin "16") (pinfunction "KL_16") (pintype "passive"))
      (node (ref "MXP-B") (pin "20") (pinfunction "KL_20") (pintype "passive"))
      (node (ref "MXP-B") (pin "24") (pinfunction "KL_24") (pintype "passive"))
      (node (ref "MXP-B") (pin "28") (pinfunction "KL_28") (pintype "passive"))
      (node (ref "MXP-B") (pin "30") (pinfunction "KL_30") (pintype "passive"))
      (node (ref "MXP-B") (pin "8") (pinfunction "KL_8") (pintype "passive"))
      (node (ref "OK1") (pin "4") (pinfunction "EMI_4") (pintype "passive"))
      (node (ref "OK2") (pin "4") (pinfunction "EMI_4") (pintype "passive"))
      (node (ref "POWER_LED") (pin "K") (pinfunction "C_K") (pintype "passive"))
      (node (ref "Q2") (pin "E") (pinfunction "E_E") (pintype "passive"))
      (node (ref "Q4") (pin "E") (pinfunction "E_E") (pintype "passive"))
      (node (ref "Q6") (pin "E") (pinfunction "E_E") (pintype "passive"))
      (node (ref "R3") (pin "1") (pinfunction "1_1") (pintype "passive"))
      (node (ref "R4") (pin "1") (pinfunction "1_1") (pintype "passive"))
      (node (ref "SHUTTER") (pin "P$GND0") (pinfunction "GND0_P$GND0") (pintype "bidirectional"))
      (node (ref "SHUTTER") (pin "P$GND1") (pinfunction "GND1_P$GND1") (pintype "bidirectional"))
      (node (ref "SLN") (pin "P$GND0") (pinfunction "GND0_P$GND0") (pintype "bidirectional"))
      (node (ref "SLN") (pin "P$GND1") (pinfunction "GND1_P$GND1") (pintype "bidirectional"))
      (node (ref "T1") (pin "3") (pinfunction "S_3") (pintype "passive"))
      (node (ref "T2") (pin "3") (pinfunction "S_3") (pintype "passive"))
      (node (ref "U1") (pin "4") (pinfunction "GND_4") (pintype "passive"))
    )
    (net (code "57") (name "GND-ISO") (class "Default")
      (node (ref "BAT1") (pin "-") (pinfunction "-_-") (pintype "power_in"))
      (node (ref "C8") (pin "2") (pinfunction "2_2") (pintype "passive"))
      (node (ref "C9") (pin "2") (pinfunction "2_2") (pintype "passive"))
      (node (ref "GND-ISO") (pin "TP") (pinfunction "TP_TP") (pintype "input"))
      (node (ref "LICK_INPUTS") (pin "P$GND0") (pinfunction "GND0_P$GND0") (pintype "bidirectional"))
      (node (ref "LICK_INPUTS") (pin "P$GND1") (pinfunction "GND1_P$GND1") (pintype "bidirectional"))
      (node (ref "OK1") (pin "2") (pinfunction "C_2") (pintype "passive"))
      (node (ref "OK2") (pin "2") (pinfunction "C_2") (pintype "passive"))
      (node (ref "R17") (pin "2") (pinfunction "2_2") (pintype "passive"))
      (node (ref "R18") (pin "2") (pinfunction "2_2") (pintype "passive"))
      (node (ref "S2") (pin "5") (pinfunction "P2_5") (pintype "passive"))
      (node (ref "TSH_L") (pin "A") (pinfunction "A_A") (pintype "passive"))
      (node (ref "TSH_R") (pin "A") (pinfunction "A_A") (pintype "passive"))
      (node (ref "U2") (pin "1") (pinfunction "GND_1") (pintype "passive"))
      (node (ref "U2") (pin "2") (pinfunction "V-_2") (pintype "power_in"))
      (node (ref "U3") (pin "1") (pinfunction "GND_1") (pintype "passive"))
      (node (ref "U3") (pin "2") (pinfunction "V-_2") (pintype "power_in"))
    )
    (net (code "58") (name "LICK_L_IN") (class "Default")
      (node (ref "LICK_INPUTS") (pin "P$SIG0") (pinfunction "SIG0_P$SIG0") (pintype "bidirectional"))
      (node (ref "R15") (pin "1") (pinfunction "1_1") (pintype "passive"))
      (node (ref "U2") (pin "4") (pinfunction "IN-_4") (pintype "input"))
    )
    (net (code "59") (name "LICK_R_IN") (class "Default")
      (node (ref "LICK_INPUTS") (pin "P$SIG1") (pinfunction "SIG1_P$SIG1") (pintype "bidirectional"))
      (node (ref "R16") (pin "1") (pinfunction "1_1") (pintype "passive"))
      (node (ref "U3") (pin "4") (pinfunction "IN-_4") (pintype "input"))
    )
    (net (code "60") (name "N$6") (class "Default")
      (node (ref "R2") (pin "2") (pinfunction "2_2") (pintype "passive"))
      (node (ref "R4") (pin "2") (pinfunction "2_2") (pintype "passive"))
      (node (ref "T1") (pin "1") (pinfunction "G_1") (pintype "passive"))
    )
    (net (code "61") (name "N$16") (class "Default")
      (node (ref "BUCKPUCK1") (pin "VIN+") (pinfunction "VIN+_VIN+") (pintype "bidirectional"))
      (node (ref "BUCKPUCK2") (pin "VIN+") (pinfunction "VIN+_VIN+") (pintype "bidirectional"))
      (node (ref "BUCKPUCK3") (pin "VIN+") (pinfunction "VIN+_VIN+") (pintype "bidirectional"))
      (node (ref "C1") (pin "+") (pinfunction "+_+") (pintype "passive"))
      (node (ref "C2") (pin "+") (pinfunction "+_+") (pintype "passive"))
      (node (ref "C3") (pin "+") (pinfunction "+_+") (pintype "passive"))
      (node (ref "C4") (pin "+") (pinfunction "+_+") (pintype "passive"))
      (node (ref "D1") (pin "C") (pinfunction "C_C") (pintype "passive"))
      (node (ref "U1") (pin "1") (pinfunction "VI_1") (pintype "input"))
      (node (ref "VIN") (pin "TP") (pinfunction "TP_TP") (pintype "input"))
    )
    (net (code "62") (name "Net-(AUDIO-GND0)") (class "Default")
      (node (ref "AUDIO") (pin "P$GND0") (pinfunction "GND0_P$GND0") (pintype "bidirectional"))
      (node (ref "AUDIO") (pin "P$GND1") (pinfunction "GND1_P$GND1") (pintype "bidirectional"))
      (node (ref "JP1") (pin "SLEEVE") (pinfunction "SLEEVE_SLEEVE") (pintype "bidirectional"))
      (node (ref "JP2") (pin "SLEEVE") (pinfunction "SLEEVE_SLEEVE") (pintype "bidirectional"))
    )
    (net (code "63") (name "Net-(AUDIO-SIG0)") (class "Default")
      (node (ref "AUDIO") (pin "P$SIG0") (pinfunction "SIG0_P$SIG0") (pintype "bidirectional"))
      (node (ref "JP1") (pin "RING") (pinfunction "RIGHT_RING") (pintype "bidirectional"))
      (node (ref "JP2") (pin "RING") (pinfunction "RIGHT_RING") (pintype "bidirectional"))
    )
    (net (code "64") (name "Net-(AUDIO-SIG1)") (class "Default")
      (node (ref "AUDIO") (pin "P$SIG1") (pinfunction "SIG1_P$SIG1") (pintype "bidirectional"))
      (node (ref "JP1") (pin "TIP") (pinfunction "LEFT_TIP") (pintype "bidirectional"))
      (node (ref "JP2") (pin "TIP") (pinfunction "LEFT_TIP") (pintype "bidirectional"))
    )
    (net (code "65") (name "Net-(BUCKPUCK1-PadCTRL)") (class "Default")
      (node (ref "BUCKPUCK1") (pin "CTRL") (pinfunction "CTRL_CTRL") (pintype "bidirectional"))
      (node (ref "Q1") (pin "C") (pinfunction "C_C") (pintype "passive"))
    )
    (net (code "66") (name "Net-(BUCKPUCK1-PadREF)") (class "Default")
      (node (ref "BUCKPUCK1") (pin "REF") (pinfunction "REF_REF") (pintype "bidirectional"))
      (node (ref "Q1") (pin "E") (pinfunction "E_E") (pintype "passive"))
      (node (ref "R6") (pin "1") (pinfunction "1_1") (pintype "passive"))
    )
    (net (code "67") (name "Net-(BUCKPUCK2-PadCTRL)") (class "Default")
      (node (ref "BUCKPUCK2") (pin "CTRL") (pinfunction "CTRL_CTRL") (pintype "bidirectional"))
      (node (ref "Q3") (pin "C") (pinfunction "C_C") (pintype "passive"))
    )
    (net (code "68") (name "Net-(BUCKPUCK2-PadREF)") (class "Default")
      (node (ref "BUCKPUCK2") (pin "REF") (pinfunction "REF_REF") (pintype "bidirectional"))
      (node (ref "Q3") (pin "E") (pinfunction "E_E") (pintype "passive"))
      (node (ref "R7") (pin "1") (pinfunction "1_1") (pintype "passive"))
    )
    (net (code "69") (name "Net-(BUCKPUCK3-PadCTRL)") (class "Default")
      (node (ref "BUCKPUCK3") (pin "CTRL") (pinfunction "CTRL_CTRL") (pintype "bidirectional"))
      (node (ref "Q5") (pin "C") (pinfunction "C_C") (pintype "passive"))
    )
    (net (code "70") (name "Net-(BUCKPUCK3-PadREF)") (class "Default")
      (node (ref "BUCKPUCK3") (pin "REF") (pinfunction "REF_REF") (pintype "bidirectional"))
      (node (ref "Q5") (pin "E") (pinfunction "E_E") (pintype "passive"))
      (node (ref "R8") (pin "1") (pinfunction "1_1") (pintype "passive"))
    )
    (net (code "71") (name "Net-(CH1-1)") (class "Default")
      (node (ref "BUCKPUCK1") (pin "LED+") (pinfunction "LED+_LED+") (pintype "bidirectional"))
      (node (ref "CH1") (pin "P1") (pinfunction "1_P1") (pintype "passive"))
    )
    (net (code "72") (name "Net-(CH2-1)") (class "Default")
      (node (ref "BUCKPUCK2") (pin "LED+") (pinfunction "LED+_LED+") (pintype "bidirectional"))
      (node (ref "CH2") (pin "P1") (pinfunction "1_P1") (pintype "passive"))
    )
    (net (code "73") (name "Net-(CH3-1)") (class "Default")
      (node (ref "BUCKPUCK3") (pin "LED+") (pinfunction "LED+_LED+") (pintype "bidirectional"))
      (node (ref "CH3") (pin "P1") (pinfunction "1_P1") (pintype "passive"))
    )
    (net (code "74") (name "Net-(D2-C)") (class "Default")
      (node (ref "D2") (pin "A") (pinfunction "C_A") (pintype "passive"))
      (node (ref "J1") (pin "2") (pinfunction "2_2") (pintype "passive"))
      (node (ref "T1") (pin "2") (pinfunction "D_2") (pintype "passive"))
      (node (ref "T1") (pin "4") (pinfunction "D_4") (pintype "passive"))
    )
    (net (code "75") (name "Net-(D3-C)") (class "Default")
      (node (ref "D3") (pin "A") (pinfunction "C_A") (pintype "passive"))
      (node (ref "J2") (pin "2") (pinfunction "2_2") (pintype "passive"))
      (node (ref "T2") (pin "2") (pinfunction "D_2") (pintype "passive"))
      (node (ref "T2") (pin "4") (pinfunction "D_4") (pintype "passive"))
    )
    (net (code "76") (name "Net-(ISOLATED-PadA)") (class "Default")
      (node (ref "ISOLATED") (pin "A") (pinfunction "A_A") (pintype "passive"))
      (node (ref "R23") (pin "1") (pinfunction "1_1") (pintype "passive"))
    )
    (net (code "77") (name "Net-(JP5-P$2)") (class "Default")
      (node (ref "J2") (pin "1") (pinfunction "1_1") (pintype "passive"))
      (node (ref "JP5") (pin "2") (pinfunction "P$2_2") (pintype "bidirectional"))
    )
    (net (code "78") (name "Net-(JP6-P$2)") (class "Default")
      (node (ref "J1") (pin "1") (pinfunction "1_1") (pintype "passive"))
      (node (ref "JP6") (pin "2") (pinfunction "P$2_2") (pintype "bidirectional"))
    )
    (net (code "79") (name "Net-(JP10-PadPWR)") (class "Default")
      (node (ref "JP10") (pin "PWR") (pinfunction "PWR_PWR") (pintype "bidirectional"))
      (node (ref "S1") (pin "2") (pinfunction "2_2") (pintype "passive"))
    )
    (net (code "80") (name "Net-(OK1-A)") (class "Default")
      (node (ref "OK1") (pin "1") (pinfunction "A_1") (pintype "passive"))
      (node (ref "R19") (pin "1") (pinfunction "1_1") (pintype "passive"))
    )
    (net (code "81") (name "Net-(OK1-COL)") (class "Default")
      (node (ref "DNP1") (pin "2") (pinfunction "2_2") (pintype "passive"))
      (node (ref "OK1") (pin "5") (pinfunction "COL_5") (pintype "passive"))
      (node (ref "R21") (pin "1") (pinfunction "1_1") (pintype "passive"))
    )
    (net (code "82") (name "Net-(OK2-A)") (class "Default")
      (node (ref "OK2") (pin "1") (pinfunction "A_1") (pintype "passive"))
      (node (ref "R20") (pin "1") (pinfunction "1_1") (pintype "passive"))
    )
    (net (code "83") (name "Net-(OK2-COL)") (class "Default")
      (node (ref "DNP2") (pin "2") (pinfunction "2_2") (pintype "passive"))
      (node (ref "OK2") (pin "5") (pinfunction "COL_5") (pintype "passive"))
      (node (ref "R22") (pin "1") (pinfunction "1_1") (pintype "passive"))
    )
    (net (code "84") (name "Net-(POWER_LED-PadA)") (class "Default")
      (node (ref "POWER_LED") (pin "A") (pinfunction "A_A") (pintype "passive"))
      (node (ref "R5") (pin "1") (pinfunction "1_1") (pintype "passive"))
    )
    (net (code "85") (name "Net-(Q1-PadB)") (class "Default")
      (node (ref "Q1") (pin "B") (pinfunction "B_B") (pintype "passive"))
      (node (ref "R6") (pin "2") (pinfunction "2_2") (pintype "passive"))
      (node (ref "R9") (pin "1") (pinfunction "1_1") (pintype "passive"))
    )
    (net (code "86") (name "Net-(Q2-PadB)") (class "Default")
      (node (ref "Q2") (pin "B") (pinfunction "B_B") (pintype "passive"))
      (node (ref "R12") (pin "1") (pinfunction "1_1") (pintype "passive"))
    )
    (net (code "87") (name "Net-(Q2-PadC)") (class "Default")
      (node (ref "Q2") (pin "C") (pinfunction "C_C") (pintype "passive"))
      (node (ref "R9") (pin "2") (pinfunction "2_2") (pintype "passive"))
    )
    (net (code "88") (name "Net-(Q3-PadB)") (class "Default")
      (node (ref "Q3") (pin "B") (pinfunction "B_B") (pintype "passive"))
      (node (ref "R10") (pin "1") (pinfunction "1_1") (pintype "passive"))
      (node (ref "R7") (pin "2") (pinfunction "2_2") (pintype "passive"))
    )
    (net (code "89") (name "Net-(Q4-PadB)") (class "Default")
      (node (ref "Q4") (pin "B") (pinfunction "B_B") (pintype "passive"))
      (node (ref "R13") (pin "1") (pinfunction "1_1") (pintype "passive"))
    )
    (net (code "90") (name "Net-(Q4-PadC)") (class "Default")
      (node (ref "Q4") (pin "C") (pinfunction "C_C") (pintype "passive"))
      (node (ref "R10") (pin "2") (pinfunction "2_2") (pintype "passive"))
    )
    (net (code "91") (name "Net-(Q5-PadB)") (class "Default")
      (node (ref "Q5") (pin "B") (pinfunction "B_B") (pintype "passive"))
      (node (ref "R11") (pin "1") (pinfunction "1_1") (pintype "passive"))
      (node (ref "R8") (pin "2") (pinfunction "2_2") (pintype "passive"))
    )
    (net (code "92") (name "Net-(Q6-PadB)") (class "Default")
      (node (ref "Q6") (pin "B") (pinfunction "B_B") (pintype "passive"))
      (node (ref "R14") (pin "1") (pinfunction "1_1") (pintype "passive"))
    )
    (net (code "93") (name "Net-(Q6-PadC)") (class "Default")
      (node (ref "Q6") (pin "C") (pinfunction "C_C") (pintype "passive"))
      (node (ref "R11") (pin "2") (pinfunction "2_2") (pintype "passive"))
    )
    (net (code "94") (name "Net-(S2-P3)") (class "Default")
      (node (ref "BAT1") (pin "+") (pinfunction "+_+") (pintype "power_in"))
      (node (ref "S2") (pin "8") (pinfunction "P3_8") (pintype "passive"))
    )
    (net (code "95") (name "Net-(S2-S1)") (class "Default")
      (node (ref "R23") (pin "2") (pinfunction "2_2") (pintype "passive"))
      (node (ref "S2") (pin "3") (pinfunction "S1_3") (pintype "passive"))
    )
    (net (code "96") (name "Net-(T2-G)") (class "Default")
      (node (ref "R1") (pin "2") (pinfunction "2_2") (pintype "passive"))
      (node (ref "R3") (pin "2") (pinfunction "2_2") (pintype "passive"))
      (node (ref "T2") (pin "1") (pinfunction "G_1") (pintype "passive"))
    )
    (net (code "97") (name "Net-(U2-HYST)") (class "Default")
      (node (ref "HYST_L") (pin "E") (pinfunction "E_E") (pintype "passive"))
      (node (ref "R17") (pin "1") (pinfunction "1_1") (pintype "passive"))
      (node (ref "U2") (pin "5") (pinfunction "HYST_5") (pintype "input"))
    )
    (net (code "98") (name "Net-(U2-IN+)") (class "Default")
      (node (ref "TSH_L") (pin "S") (pinfunction "S_S") (pintype "passive"))
      (node (ref "U2") (pin "3") (pinfunction "IN+_3") (pintype "input"))
    )
    (net (code "99") (name "Net-(U2-OUT)") (class "Default")
      (node (ref "R19") (pin "2") (pinfunction "2_2") (pintype "passive"))
      (node (ref "U2") (pin "8") (pinfunction "OUT_8") (pintype "output"))
    )
    (net (code "100") (name "Net-(U2-REF)") (class "Default")
      (node (ref "HYST_L") (pin "A") (pinfunction "A_A") (pintype "passive"))
      (node (ref "HYST_L") (pin "S") (pinfunction "S_S") (pintype "passive"))
      (node (ref "U2") (pin "6") (pinfunction "REF_6") (pintype "output"))
    )
    (net (code "101") (name "Net-(U3-HYST)") (class "Default")
      (node (ref "HYST_R") (pin "E") (pinfunction "E_E") (pintype "passive"))
      (node (ref "R18") (pin "1") (pinfunction "1_1") (pintype "passive"))
      (node (ref "U3") (pin "5") (pinfunction "HYST_5") (pintype "input"))
    )
    (net (code "102") (name "Net-(U3-IN+)") (class "Default")
      (node (ref "TSH_R") (pin "S") (pinfunction "S_S") (pintype "passive"))
      (node (ref "U3") (pin "3") (pinfunction "IN+_3") (pintype "input"))
    )
    (net (code "103") (name "Net-(U3-OUT)") (class "Default")
      (node (ref "R20") (pin "2") (pinfunction "2_2") (pintype "passive"))
      (node (ref "U3") (pin "8") (pinfunction "OUT_8") (pintype "output"))
    )
    (net (code "104") (name "Net-(U3-REF)") (class "Default")
      (node (ref "HYST_R") (pin "A") (pinfunction "A_A") (pintype "passive"))
      (node (ref "HYST_R") (pin "S") (pinfunction "S_S") (pintype "passive"))
      (node (ref "U3") (pin "6") (pinfunction "REF_6") (pintype "output"))
    )
    (net (code "105") (name "VCC") (class "Default")
      (node (ref "C5") (pin "+") (pinfunction "+_+") (pintype "passive"))
      (node (ref "D2") (pin "C") (pinfunction "A_C") (pintype "passive"))
      (node (ref "D3") (pin "C") (pinfunction "A_C") (pintype "passive"))
      (node (ref "JP5") (pin "1") (pinfunction "P$1_1") (pintype "bidirectional"))
      (node (ref "JP6") (pin "1") (pinfunction "P$1_1") (pintype "bidirectional"))
      (node (ref "R5") (pin "2") (pinfunction "2_2") (pintype "passive"))
      (node (ref "U1") (pin "3") (pinfunction "VO_3") (pintype "passive"))
      (node (ref "VSOLN") (pin "TP") (pinfunction "TP_TP") (pintype "input"))
    )
    (net (code "106") (name "VIN") (class "Default")
      (node (ref "D1") (pin "A") (pinfunction "A_A") (pintype "passive"))
      (node (ref "S1") (pin "1") (pinfunction "1_1") (pintype "passive"))
    )
    (net (code "107") (name "unconnected-(OK1-BAS-Pad6)") (class "Default")
      (node (ref "OK1") (pin "6") (pinfunction "BAS_6") (pintype "passive"))
    )
    (net (code "108") (name "unconnected-(OK2-BAS-Pad6)") (class "Default")
      (node (ref "OK2") (pin "6") (pinfunction "BAS_6") (pintype "passive"))
    )
    (net (code "109") (name "unconnected-(S1-Pad3)") (class "Default")
      (node (ref "S1") (pin "3") (pinfunction "3_3") (pintype "passive"))
    )
    (net (code "110") (name "unconnected-(S2-O3-Pad7)") (class "Default")
      (node (ref "S2") (pin "7") (pinfunction "O3_7") (pintype "passive"))
    )
    (net (code "111") (name "unconnected-(S2-S2-Pad6)") (class "Default")
      (node (ref "S2") (pin "6") (pinfunction "S2_6") (pintype "passive"))
    )
  )
)
